# power.net
KiCad netlist of a schematic drawn in Altium Designer
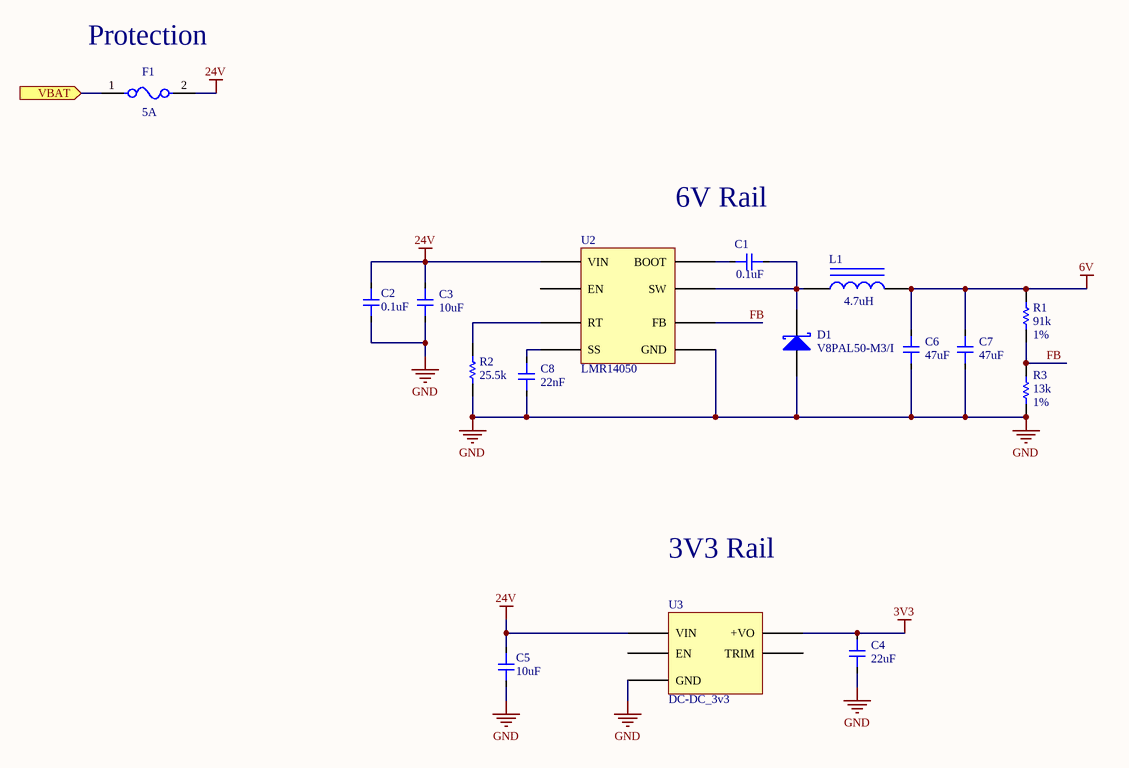
[diagram p0: power.SchDoc]

(export (version "E")
  (design (tool "Eeschema 10.0.6"))
  (components
    (comp (ref "C1")
      (value "value")
      (footprint "CAP 0805 L")
      (description "CAP CER 0.1UF 50V X7R 0805")
      (fields
        (field (name "MANUFACTURER") "Samsung")
        (field (name "MANUFACTURER PART NUMBER") "CL21B104KBC5PNL")
        (field (name "CAPACITANCE") "0.1uF")
      )
      (libsource (lib "streetbot") (part "CAP 0805"))
    )
    (comp (ref "C2")
      (value "value")
      (footprint "CAP 0805 L")
      (description "CAP CER 0.1UF 50V X7R 0805")
      (fields
        (field (name "MANUFACTURER") "Samsung")
        (field (name "MANUFACTURER PART NUMBER") "CL21B104KBC5PNL")
        (field (name "CAPACITANCE") "0.1uF")
      )
      (libsource (lib "streetbot") (part "CAP 0805"))
    )
    (comp (ref "C3")
      (value "value")
      (footprint "1210")
      (description "TDK - C3225X7R1H106M250AC - C3225X7R1H106MT000E")
      (fields
        (field (name "MANUFACTURER") "TDK")
        (field (name "MANUFACTURER PART NUMBER") "C3225X7R1H106M250AC")
        (field (name "CAPACITANCE") "10uF")
      )
      (libsource (lib "streetbot") (part "CAP 0805"))
    )
    (comp (ref "C4")
      (value "value")
      (footprint "CAP 0805 L")
      (description "CAP CER 22UF 10V X6S 0805")
      (fields
        (field (name "MANUFACTURER") "Murata")
        (field (name "MANUFACTURER PART NUMBER") "GRT21BC81A226ME13L")
        (field (name "CAPACITANCE") "22uF")
      )
      (libsource (lib "streetbot") (part "CAP 0805"))
    )
    (comp (ref "C5")
      (value "value")
      (footprint "1206_CAP")
      (fields
        (field (name "MANUFACTURER") "Murata")
        (field (name "MANUFACTURER PART NUMBER") "GRT31CR61H106KE01L")
        (field (name "CAPACITANCE") "10uF")
        (field (name "TOLERANCE") "10%")
      )
      (libsource (lib "streetbot") (part "CAP 0805"))
    )
    (comp (ref "C6")
      (value "value")
      (footprint "1210")
      (description "KEMET - C1210C476M4PACTU. - CAPACITOR CERAMIC 47UF, 16V, X5R, 1210")
      (fields
        (field (name "MANUFACTURER") "KEMET")
        (field (name "MANUFACTURER PART NUMBER") "C1210C476M4PACTU")
        (field (name "CAPACITANCE") "47uF")
      )
      (libsource (lib "streetbot") (part "CAP 0805"))
    )
    (comp (ref "C7")
      (value "value")
      (footprint "1210")
      (description "KEMET - C1210C476M4PACTU. - CAPACITOR CERAMIC 47UF, 16V, X5R, 1210")
      (fields
        (field (name "MANUFACTURER") "KEMET")
        (field (name "MANUFACTURER PART NUMBER") "C1210C476M4PACTU")
        (field (name "CAPACITANCE") "47uF")
      )
      (libsource (lib "streetbot") (part "CAP 0805"))
    )
    (comp (ref "C8")
      (value "22nF")
      (footprint "CAP 0805 L")
      (description "CAP 0805")
      (fields (field (name "VOLTAGE") "25V") (field (name "MANUFACTURER") "Yageo"))
      (libsource (lib "streetbot") (part "CAP 0805"))
    )
    (comp (ref "D1")
      (value "D Schottky")
      (footprint "DO-221BC")
      (description "Schottky Diode")
      (fields
        (field (name "MANUFACTURER") "Vishay Semiconductors")
        (field (name "MANUFACTURER PART NUMBER") "V8PAL50-M3/I")
      )
      (libsource (lib "Miscellaneous Devices") (part "D Schottky"))
    )
    (comp (ref "F1")
      (value "0154005.DRT")
      (footprint "Littelfuse_0154_0")
      (description "FUSE BRD MNT 5A 125VAC/VDC 2SMD")
      (fields
        (field (name "MANUFACTURER") "Littelfuse")
        (field (name "MANUFACTURER PART NUMBER") "0154005DRT")
        (field (name "CURRENT RATING") "5A")
      )
      (libsource (lib "food_box") (part "0154005.DRT"))
    )
    (comp (ref "L1")
      (value "Inductor Iron")
      (footprint "SRP7050TA")
      (description "FIXED IND 4.7UH 6.5A 30.8 MOHM")
      (fields
        (field (name "MANUFACTURER") "Bourns")
        (field (name "MANUFACTURER PART NUMBER") "SRP7050TA-4R7M")
        (field (name "INDUCTANCE") "4.7uH")
      )
      (libsource (lib "Miscellaneous Devices") (part "Inductor Iron"))
    )
    (comp (ref "R1")
      (value "Res1")
      (footprint "RES 0603 L")
      (description "Res Thick Film 0603 91K Ohm 1% 1/10W ±100ppm/°C Molded SMD SMD Paper T/R")
      (fields
        (field (name "MANUFACTURER") "Vishay")
        (field (name "MANUFACTURER PART NUMBER") "CRCW060391K0FKEA")
        (field (name "RESISTANCE") "91k")
        (field (name "TOLERANCE") "1%")
      )
      (libsource (lib "Miscellaneous Devices") (part "Res1"))
    )
    (comp (ref "R2")
      (value "Res1")
      (footprint "RES 0603 L")
      (description "RES SMD 25.5K OHM 1% 1/10W 0603")
      (fields
        (field (name "MANUFACTURER") "Vishay")
        (field (name "MANUFACTURER PART NUMBER") "CRCW060325K5FKEA")
        (field (name "RESISTANCE") "25.5k")
      )
      (libsource (lib "Miscellaneous Devices") (part "Res1"))
    )
    (comp (ref "R3")
      (value "Res1")
      (footprint "RES 0603 L")
      (description "Res Thick Film 0603 13K Ohm 1% 1/10W 100ppm/C Molded SMD SMD Paper T/R")
      (fields
        (field (name "MANUFACTURER") "Vishay Dale")
        (field (name "MANUFACTURER PART NUMBER") "CRCW060313K0FKTA")
        (field (name "RESISTANCE") "13k")
        (field (name "TOLERANCE") "1%")
      )
      (libsource (lib "Miscellaneous Devices") (part "Res1"))
    )
    (comp (ref "U2") (value "LMR14050") (footprint "HSOIC-8") (libsource (lib "powerhub") (part "LMR14050")))
    (comp (ref "U3")
      (value "DC-DC_3v3")
      (footprint "V78E-1000-SMT")
      (libsource (lib "food_box") (part "DC-DC_3v3"))
    )
  )
  (nets
    (net (code "1") (name "/FB") (class "Default")
      (node (ref "R1") (pin "1") (pinfunction "1_1") (pintype "passive"))
      (node (ref "R3") (pin "2") (pinfunction "2_2") (pintype "passive"))
      (node (ref "U2") (pin "5") (pinfunction "FB_5") (pintype "passive"))
    )
    (net (code "2") (name "/VBAT") (class "Default")
      (node (ref "F1") (pin "1") (pinfunction "1_1") (pintype "passive"))
    )
    (net (code "3") (name "3V3") (class "Default")
      (node (ref "C4") (pin "2") (pinfunction "2_2") (pintype "passive"))
      (node (ref "U3") (pin "4") (pinfunction "+VO_4") (pintype "passive"))
    )
    (net (code "4") (name "6V") (class "Default")
      (node (ref "C6") (pin "2") (pinfunction "2_2") (pintype "passive"))
      (node (ref "C7") (pin "2") (pinfunction "2_2") (pintype "passive"))
      (node (ref "L1") (pin "2") (pinfunction "2_2") (pintype "passive"))
      (node (ref "R1") (pin "2") (pinfunction "2_2") (pintype "passive"))
    )
    (net (code "5") (name "24V") (class "Default")
      (node (ref "C2") (pin "2") (pinfunction "2_2") (pintype "passive"))
      (node (ref "C3") (pin "2") (pinfunction "2_2") (pintype "passive"))
      (node (ref "C5") (pin "2") (pinfunction "2_2") (pintype "passive"))
      (node (ref "F1") (pin "2") (pinfunction "2_2") (pintype "passive"))
      (node (ref "U2") (pin "2") (pinfunction "VIN_2") (pintype "passive"))
      (node (ref "U3") (pin "3") (pinfunction "VIN_3") (pintype "passive"))
    )
    (net (code "6") (name "GND") (class "Default")
      (node (ref "C2") (pin "1") (pinfunction "1_1") (pintype "passive"))
      (node (ref "C3") (pin "1") (pinfunction "1_1") (pintype "passive"))
      (node (ref "C4") (pin "1") (pinfunction "1_1") (pintype "passive"))
      (node (ref "C5") (pin "1") (pinfunction "1_1") (pintype "passive"))
      (node (ref "C6") (pin "1") (pinfunction "1_1") (pintype "passive"))
      (node (ref "C7") (pin "1") (pinfunction "1_1") (pintype "passive"))
      (node (ref "C8") (pin "1") (pinfunction "1_1") (pintype "passive"))
      (node (ref "D1") (pin "1") (pinfunction "A_1") (pintype "passive"))
      (node (ref "R2") (pin "1") (pinfunction "1_1") (pintype "passive"))
      (node (ref "R3") (pin "1") (pinfunction "1_1") (pintype "passive"))
      (node (ref "U2") (pin "7") (pinfunction "GND_7") (pintype "passive"))
      (node (ref "U3") (pin "2") (pinfunction "GND_2") (pintype "power_in"))
    )
    (net (code "7") (name "Net-(D1-K)") (class "Default")
      (node (ref "C1") (pin "2") (pinfunction "2_2") (pintype "passive"))
      (node (ref "D1") (pin "2") (pinfunction "K_2") (pintype "passive"))
      (node (ref "L1") (pin "1") (pinfunction "1_1") (pintype "passive"))
      (node (ref "U2") (pin "8") (pinfunction "SW_8") (pintype "passive"))
    )
    (net (code "8") (name "Net-(U2-BOOT)") (class "Default")
      (node (ref "C1") (pin "1") (pinfunction "1_1") (pintype "passive"))
      (node (ref "U2") (pin "1") (pinfunction "BOOT_1") (pintype "passive"))
    )
    (net (code "9") (name "Net-(U2-RT)") (class "Default")
      (node (ref "R2") (pin "2") (pinfunction "2_2") (pintype "passive"))
      (node (ref "U2") (pin "4") (pinfunction "RT_4") (pintype "passive"))
    )
    (net (code "10") (name "Net-(U2-SS)") (class "Default")
      (node (ref "C8") (pin "2") (pinfunction "2_2") (pintype "passive"))
      (node (ref "U2") (pin "6") (pinfunction "SS_6") (pintype "passive"))
    )
    (net (code "11") (name "unconnected-(U2-EN-Pad3)") (class "Default")
      (node (ref "U2") (pin "3") (pinfunction "EN_3") (pintype "passive"))
    )
    (net (code "12") (name "unconnected-(U3-EN-Pad1)") (class "Default")
      (node (ref "U3") (pin "1") (pinfunction "EN_1") (pintype "passive"))
    )
    (net (code "13") (name "unconnected-(U3-TRIM-Pad5)") (class "Default")
      (node (ref "U3") (pin "5") (pinfunction "TRIM_5") (pintype "passive"))
    )
  )
)
